# board.net
KiCad netlist of a schematic drawn in EAGLE
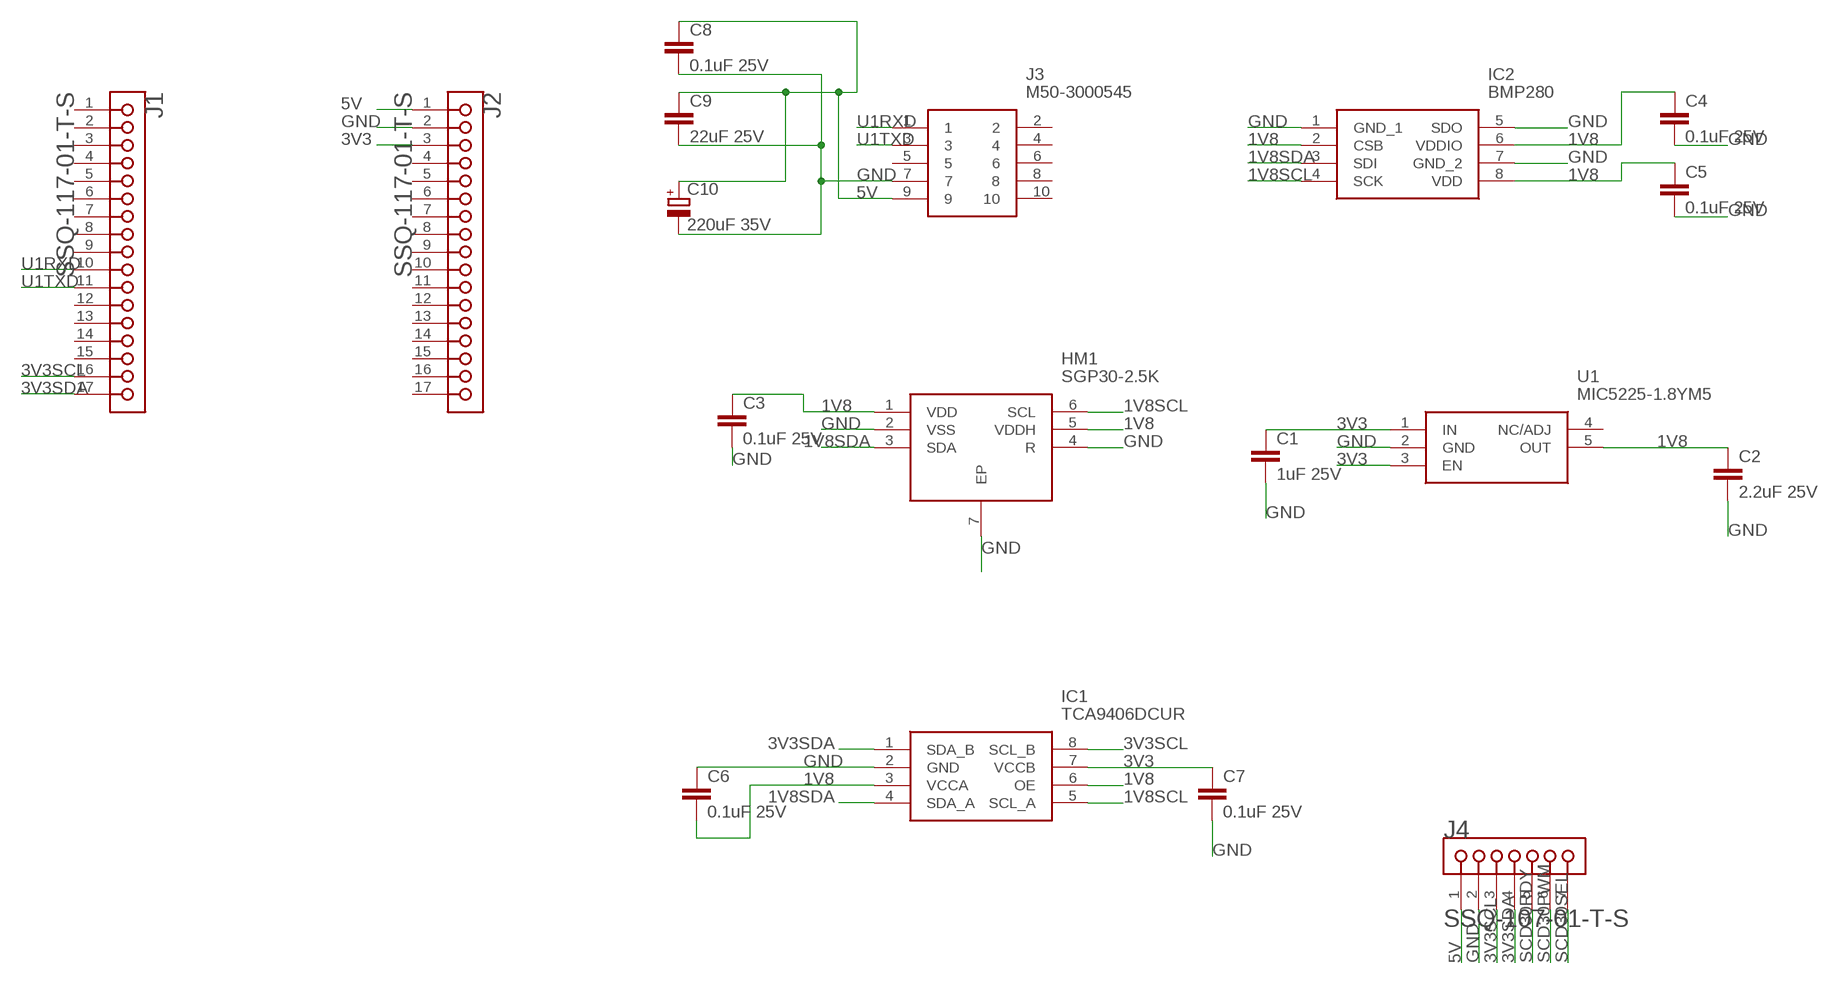
[diagram p0: schematic, sheet 1]

(export (version "E")
  (design (tool "Eeschema 10.0.6"))
  (components
    (comp (ref "C1")
      (value "1uF 25V")
      (footprint "eagle-import:C0402")
      (libsource (lib "eagle-import") (part "C-EUC0402"))
    )
    (comp (ref "C2")
      (value "2.2uF 25V")
      (footprint "eagle-import:C0402")
      (libsource (lib "eagle-import") (part "C-EUC0402"))
    )
    (comp (ref "C3")
      (value "0.1uF 25V")
      (footprint "eagle-import:C0402")
      (libsource (lib "eagle-import") (part "C-EUC0402"))
    )
    (comp (ref "C4")
      (value "0.1uF 25V")
      (footprint "eagle-import:C0402")
      (libsource (lib "eagle-import") (part "C-EUC0402"))
    )
    (comp (ref "C5")
      (value "0.1uF 25V")
      (footprint "eagle-import:C0402")
      (libsource (lib "eagle-import") (part "C-EUC0402"))
    )
    (comp (ref "C6")
      (value "0.1uF 25V")
      (footprint "eagle-import:C0402")
      (libsource (lib "eagle-import") (part "C-EUC0402"))
    )
    (comp (ref "C7")
      (value "0.1uF 25V")
      (footprint "eagle-import:C0402")
      (libsource (lib "eagle-import") (part "C-EUC0402"))
    )
    (comp (ref "C8")
      (value "0.1uF 25V")
      (footprint "eagle-import:C0402")
      (libsource (lib "eagle-import") (part "C-EUC0402"))
    )
    (comp (ref "C9")
      (value "22uF 25V")
      (footprint "eagle-import:C0805")
      (libsource (lib "eagle-import") (part "C-EUC0805"))
    )
    (comp (ref "C10")
      (value "220uF 35V")
      (footprint "eagle-import:E5-10,5")
      (libsource (lib "eagle-import") (part "CPOL-EUE5-10.5"))
    )
    (comp (ref "HM1")
      (value "SGP30-2.5K")
      (footprint "eagle-import:SON80P245X245X90-7N")
      (libsource (lib "eagle-import") (part "SGP30-2.5K"))
    )
    (comp (ref "IC1")
      (value "TCA9406DCUR")
      (footprint "eagle-import:SOP50P310X90-8N")
      (fields
        (field (name "MOUSER_PART_NUMBER") "595-TCA9406DCUR")
        (field (name "RS_PART_NUMBER") "7300644P")
      )
      (libsource (lib "eagle-import") (part "TCA9406DCUR"))
    )
    (comp (ref "IC2")
      (value "BMP280")
      (footprint "eagle-import:8-PIN-METAL-LID-LGA_1")
      (fields (field (name "MOUSER_PART_NUMBER") "262-BMP280"))
      (libsource (lib "eagle-import") (part "BMP280"))
    )
    (comp (ref "J1")
      (value "SAMTEC_SSQ-117-01-T-SSAMTEC_SSQ-117-01-T-S_0_0")
      (footprint "eagle-import:SAMTEC_SSQ-117-01-T-S_0")
      (fields (field (name "MF") "Samtec") (field (name "MPN") "SSQ-117-01-T-S"))
      (libsource (lib "eagle-import") (part "SAMTEC_SSQ-117-01-T-SSAMTEC_SSQ-117-01-T-S_0_0"))
    )
    (comp (ref "J2")
      (value "SAMTEC_SSQ-117-01-T-SSAMTEC_SSQ-117-01-T-S_0_0")
      (footprint "eagle-import:SAMTEC_SSQ-117-01-T-S_0")
      (fields (field (name "MF") "Samtec") (field (name "MPN") "SSQ-117-01-T-S"))
      (libsource (lib "eagle-import") (part "SAMTEC_SSQ-117-01-T-SSAMTEC_SSQ-117-01-T-S_0_0"))
    )
    (comp (ref "J3")
      (value "M50-3000545")
      (footprint "eagle-import:SHDR10W40P127X127_2X5_675X310X")
      (fields
        (field (name "MOUSER_PART_NUMBER") "855-M50-3000545")
        (field (name "RS_PART_NUMBER") "6810692P")
      )
      (libsource (lib "eagle-import") (part "M50-3000545"))
    )
    (comp (ref "J4")
      (value "SAMTEC_SSQ-107-01-T-SSAMTEC_SSQ-107-01-T-S_0_0")
      (footprint "eagle-import:SAMTEC_SSQ-107-01-T-S_0")
      (fields (field (name "MF") "Samtec") (field (name "MPN") "SSQ-107-01-T-S"))
      (libsource (lib "eagle-import") (part "SAMTEC_SSQ-107-01-T-SSAMTEC_SSQ-107-01-T-S_0_0"))
    )
    (comp (ref "U1")
      (value "MIC5225-1.8YM5")
      (footprint "eagle-import:SOT95P280X145-5N")
      (libsource (lib "eagle-import") (part "MIC5225-1.8YM5"))
    )
  )
  (nets
    (net (code "1") (name "/1V8") (class "Default")
      (node (ref "C2") (pin "1") (pinfunction "1_1") (pintype "passive"))
      (node (ref "C3") (pin "1") (pinfunction "1_1") (pintype "passive"))
      (node (ref "C4") (pin "1") (pinfunction "1_1") (pintype "passive"))
      (node (ref "C5") (pin "1") (pinfunction "1_1") (pintype "passive"))
      (node (ref "C6") (pin "2") (pinfunction "2_2") (pintype "passive"))
      (node (ref "HM1") (pin "1") (pinfunction "VDD_1") (pintype "bidirectional"))
      (node (ref "HM1") (pin "5") (pinfunction "VDDH_5") (pintype "bidirectional"))
      (node (ref "IC1") (pin "3") (pinfunction "VCCA_3") (pintype "power_in"))
      (node (ref "IC1") (pin "6") (pinfunction "OE_6") (pintype "bidirectional"))
      (node (ref "IC2") (pin "2") (pinfunction "CSB_2") (pintype "bidirectional"))
      (node (ref "IC2") (pin "6") (pinfunction "VDDIO_6") (pintype "bidirectional"))
      (node (ref "IC2") (pin "8") (pinfunction "VDD_8") (pintype "bidirectional"))
      (node (ref "U1") (pin "5") (pinfunction "OUT_5") (pintype "bidirectional"))
    )
    (net (code "2") (name "/1V8SCL") (class "Default")
      (node (ref "HM1") (pin "6") (pinfunction "SCL_6") (pintype "bidirectional"))
      (node (ref "IC1") (pin "5") (pinfunction "SCL_A_5") (pintype "bidirectional"))
      (node (ref "IC2") (pin "4") (pinfunction "SCK_4") (pintype "bidirectional"))
    )
    (net (code "3") (name "/1V8SDA") (class "Default")
      (node (ref "HM1") (pin "3") (pinfunction "SDA_3") (pintype "bidirectional"))
      (node (ref "IC1") (pin "4") (pinfunction "SDA_A_4") (pintype "bidirectional"))
      (node (ref "IC2") (pin "3") (pinfunction "SDI_3") (pintype "bidirectional"))
    )
    (net (code "4") (name "/3V3") (class "Default")
      (node (ref "C1") (pin "1") (pinfunction "1_1") (pintype "passive"))
      (node (ref "C7") (pin "1") (pinfunction "1_1") (pintype "passive"))
      (node (ref "IC1") (pin "7") (pinfunction "VCCB_7") (pintype "power_in"))
      (node (ref "J2") (pin "3") (pinfunction "3_3") (pintype "passive"))
      (node (ref "U1") (pin "1") (pinfunction "IN_1") (pintype "bidirectional"))
      (node (ref "U1") (pin "3") (pinfunction "EN_3") (pintype "bidirectional"))
    )
    (net (code "5") (name "/3V3SCL") (class "Default")
      (node (ref "IC1") (pin "8") (pinfunction "SCL_B_8") (pintype "bidirectional"))
      (node (ref "J1") (pin "16") (pinfunction "16_16") (pintype "passive"))
      (node (ref "J4") (pin "3") (pinfunction "3_3") (pintype "passive"))
    )
    (net (code "6") (name "/3V3SDA") (class "Default")
      (node (ref "IC1") (pin "1") (pinfunction "SDA_B_1") (pintype "bidirectional"))
      (node (ref "J1") (pin "17") (pinfunction "17_17") (pintype "passive"))
      (node (ref "J4") (pin "4") (pinfunction "4_4") (pintype "passive"))
    )
    (net (code "7") (name "/5V") (class "Default")
      (node (ref "C10") (pin "+") (pinfunction "+_+") (pintype "passive"))
      (node (ref "C8") (pin "1") (pinfunction "1_1") (pintype "passive"))
      (node (ref "C9") (pin "1") (pinfunction "1_1") (pintype "passive"))
      (node (ref "J2") (pin "1") (pinfunction "1_1") (pintype "passive"))
      (node (ref "J3") (pin "9") (pinfunction "9_9") (pintype "bidirectional"))
      (node (ref "J4") (pin "1") (pinfunction "1_1") (pintype "passive"))
    )
    (net (code "8") (name "/GND") (class "Default")
      (node (ref "C1") (pin "2") (pinfunction "2_2") (pintype "passive"))
      (node (ref "C10") (pin "-") (pinfunction "-_-") (pintype "passive"))
      (node (ref "C2") (pin "2") (pinfunction "2_2") (pintype "passive"))
      (node (ref "C3") (pin "2") (pinfunction "2_2") (pintype "passive"))
      (node (ref "C4") (pin "2") (pinfunction "2_2") (pintype "passive"))
      (node (ref "C5") (pin "2") (pinfunction "2_2") (pintype "passive"))
      (node (ref "C6") (pin "1") (pinfunction "1_1") (pintype "passive"))
      (node (ref "C7") (pin "2") (pinfunction "2_2") (pintype "passive"))
      (node (ref "C8") (pin "2") (pinfunction "2_2") (pintype "passive"))
      (node (ref "C9") (pin "2") (pinfunction "2_2") (pintype "passive"))
      (node (ref "HM1") (pin "2") (pinfunction "VSS_2") (pintype "bidirectional"))
      (node (ref "HM1") (pin "4") (pinfunction "R_4") (pintype "bidirectional"))
      (node (ref "HM1") (pin "7") (pinfunction "EP_7") (pintype "bidirectional"))
      (node (ref "IC1") (pin "2") (pinfunction "GND_2") (pintype "power_in"))
      (node (ref "IC2") (pin "1") (pinfunction "GND_1_1") (pintype "bidirectional"))
      (node (ref "IC2") (pin "5") (pinfunction "SDO_5") (pintype "bidirectional"))
      (node (ref "IC2") (pin "7") (pinfunction "GND_2_7") (pintype "bidirectional"))
      (node (ref "J2") (pin "2") (pinfunction "2_2") (pintype "passive"))
      (node (ref "J3") (pin "7") (pinfunction "7_7") (pintype "bidirectional"))
      (node (ref "J4") (pin "2") (pinfunction "2_2") (pintype "passive"))
      (node (ref "U1") (pin "2") (pinfunction "GND_2") (pintype "bidirectional"))
    )
    (net (code "9") (name "/SCD30PWM") (class "Default")
      (node (ref "J4") (pin "6") (pinfunction "6_6") (pintype "passive"))
    )
    (net (code "10") (name "/SCD30RDY") (class "Default")
      (node (ref "J4") (pin "5") (pinfunction "5_5") (pintype "passive"))
    )
    (net (code "11") (name "/SCD30SEL") (class "Default")
      (node (ref "J4") (pin "7") (pinfunction "7_7") (pintype "passive"))
    )
    (net (code "12") (name "/U1RXD") (class "Default")
      (node (ref "J1") (pin "10") (pinfunction "10_10") (pintype "passive"))
      (node (ref "J3") (pin "1") (pinfunction "1_1") (pintype "bidirectional"))
    )
    (net (code "13") (name "/U1TXD") (class "Default")
      (node (ref "J1") (pin "11") (pinfunction "11_11") (pintype "passive"))
      (node (ref "J3") (pin "3") (pinfunction "3_3") (pintype "bidirectional"))
    )
    (net (code "14") (name "unconnected-(J1-Pad1)") (class "Default")
      (node (ref "J1") (pin "1") (pinfunction "1_1") (pintype "passive"))
    )
    (net (code "15") (name "unconnected-(J1-Pad2)") (class "Default")
      (node (ref "J1") (pin "2") (pinfunction "2_2") (pintype "passive"))
    )
    (net (code "16") (name "unconnected-(J1-Pad3)") (class "Default")
      (node (ref "J1") (pin "3") (pinfunction "3_3") (pintype "passive"))
    )
    (net (code "17") (name "unconnected-(J1-Pad4)") (class "Default")
      (node (ref "J1") (pin "4") (pinfunction "4_4") (pintype "passive"))
    )
    (net (code "18") (name "unconnected-(J1-Pad5)") (class "Default")
      (node (ref "J1") (pin "5") (pinfunction "5_5") (pintype "passive"))
    )
    (net (code "19") (name "unconnected-(J1-Pad6)") (class "Default")
      (node (ref "J1") (pin "6") (pinfunction "6_6") (pintype "passive"))
    )
    (net (code "20") (name "unconnected-(J1-Pad7)") (class "Default")
      (node (ref "J1") (pin "7") (pinfunction "7_7") (pintype "passive"))
    )
    (net (code "21") (name "unconnected-(J1-Pad8)") (class "Default")
      (node (ref "J1") (pin "8") (pinfunction "8_8") (pintype "passive"))
    )
    (net (code "22") (name "unconnected-(J1-Pad9)") (class "Default")
      (node (ref "J1") (pin "9") (pinfunction "9_9") (pintype "passive"))
    )
    (net (code "23") (name "unconnected-(J1-Pad12)") (class "Default")
      (node (ref "J1") (pin "12") (pinfunction "12_12") (pintype "passive"))
    )
    (net (code "24") (name "unconnected-(J1-Pad13)") (class "Default")
      (node (ref "J1") (pin "13") (pinfunction "13_13") (pintype "passive"))
    )
    (net (code "25") (name "unconnected-(J1-Pad14)") (class "Default")
      (node (ref "J1") (pin "14") (pinfunction "14_14") (pintype "passive"))
    )
    (net (code "26") (name "unconnected-(J1-Pad15)") (class "Default")
      (node (ref "J1") (pin "15") (pinfunction "15_15") (pintype "passive"))
    )
    (net (code "27") (name "unconnected-(J2-Pad4)") (class "Default")
      (node (ref "J2") (pin "4") (pinfunction "4_4") (pintype "passive"))
    )
    (net (code "28") (name "unconnected-(J2-Pad5)") (class "Default")
      (node (ref "J2") (pin "5") (pinfunction "5_5") (pintype "passive"))
    )
    (net (code "29") (name "unconnected-(J2-Pad6)") (class "Default")
      (node (ref "J2") (pin "6") (pinfunction "6_6") (pintype "passive"))
    )
    (net (code "30") (name "unconnected-(J2-Pad7)") (class "Default")
      (node (ref "J2") (pin "7") (pinfunction "7_7") (pintype "passive"))
    )
    (net (code "31") (name "unconnected-(J2-Pad8)") (class "Default")
      (node (ref "J2") (pin "8") (pinfunction "8_8") (pintype "passive"))
    )
    (net (code "32") (name "unconnected-(J2-Pad9)") (class "Default")
      (node (ref "J2") (pin "9") (pinfunction "9_9") (pintype "passive"))
    )
    (net (code "33") (name "unconnected-(J2-Pad10)") (class "Default")
      (node (ref "J2") (pin "10") (pinfunction "10_10") (pintype "passive"))
    )
    (net (code "34") (name "unconnected-(J2-Pad11)") (class "Default")
      (node (ref "J2") (pin "11") (pinfunction "11_11") (pintype "passive"))
    )
    (net (code "35") (name "unconnected-(J2-Pad12)") (class "Default")
      (node (ref "J2") (pin "12") (pinfunction "12_12") (pintype "passive"))
    )
    (net (code "36") (name "unconnected-(J2-Pad13)") (class "Default")
      (node (ref "J2") (pin "13") (pinfunction "13_13") (pintype "passive"))
    )
    (net (code "37") (name "unconnected-(J2-Pad14)") (class "Default")
      (node (ref "J2") (pin "14") (pinfunction "14_14") (pintype "passive"))
    )
    (net (code "38") (name "unconnected-(J2-Pad15)") (class "Default")
      (node (ref "J2") (pin "15") (pinfunction "15_15") (pintype "passive"))
    )
    (net (code "39") (name "unconnected-(J2-Pad16)") (class "Default")
      (node (ref "J2") (pin "16") (pinfunction "16_16") (pintype "passive"))
    )
    (net (code "40") (name "unconnected-(J2-Pad17)") (class "Default")
      (node (ref "J2") (pin "17") (pinfunction "17_17") (pintype "passive"))
    )
    (net (code "41") (name "unconnected-(J3-Pad2)") (class "Default")
      (node (ref "J3") (pin "2") (pinfunction "2_2") (pintype "bidirectional"))
    )
    (net (code "42") (name "unconnected-(J3-Pad4)") (class "Default")
      (node (ref "J3") (pin "4") (pinfunction "4_4") (pintype "bidirectional"))
    )
    (net (code "43") (name "unconnected-(J3-Pad5)") (class "Default")
      (node (ref "J3") (pin "5") (pinfunction "5_5") (pintype "bidirectional"))
    )
    (net (code "44") (name "unconnected-(J3-Pad6)") (class "Default")
      (node (ref "J3") (pin "6") (pinfunction "6_6") (pintype "bidirectional"))
    )
    (net (code "45") (name "unconnected-(J3-Pad8)") (class "Default")
      (node (ref "J3") (pin "8") (pinfunction "8_8") (pintype "bidirectional"))
    )
    (net (code "46") (name "unconnected-(J3-Pad10)") (class "Default")
      (node (ref "J3") (pin "10") (pinfunction "10_10") (pintype "bidirectional"))
    )
    (net (code "47") (name "unconnected-(U1-NC{slash}ADJ-Pad4)") (class "Default")
      (node (ref "U1") (pin "4") (pinfunction "NC/ADJ_4") (pintype "bidirectional"))
    )
  )
)
